# Lab_1_Schematic.net
KiCad netlist of a schematic drawn in EasyEDA Pro
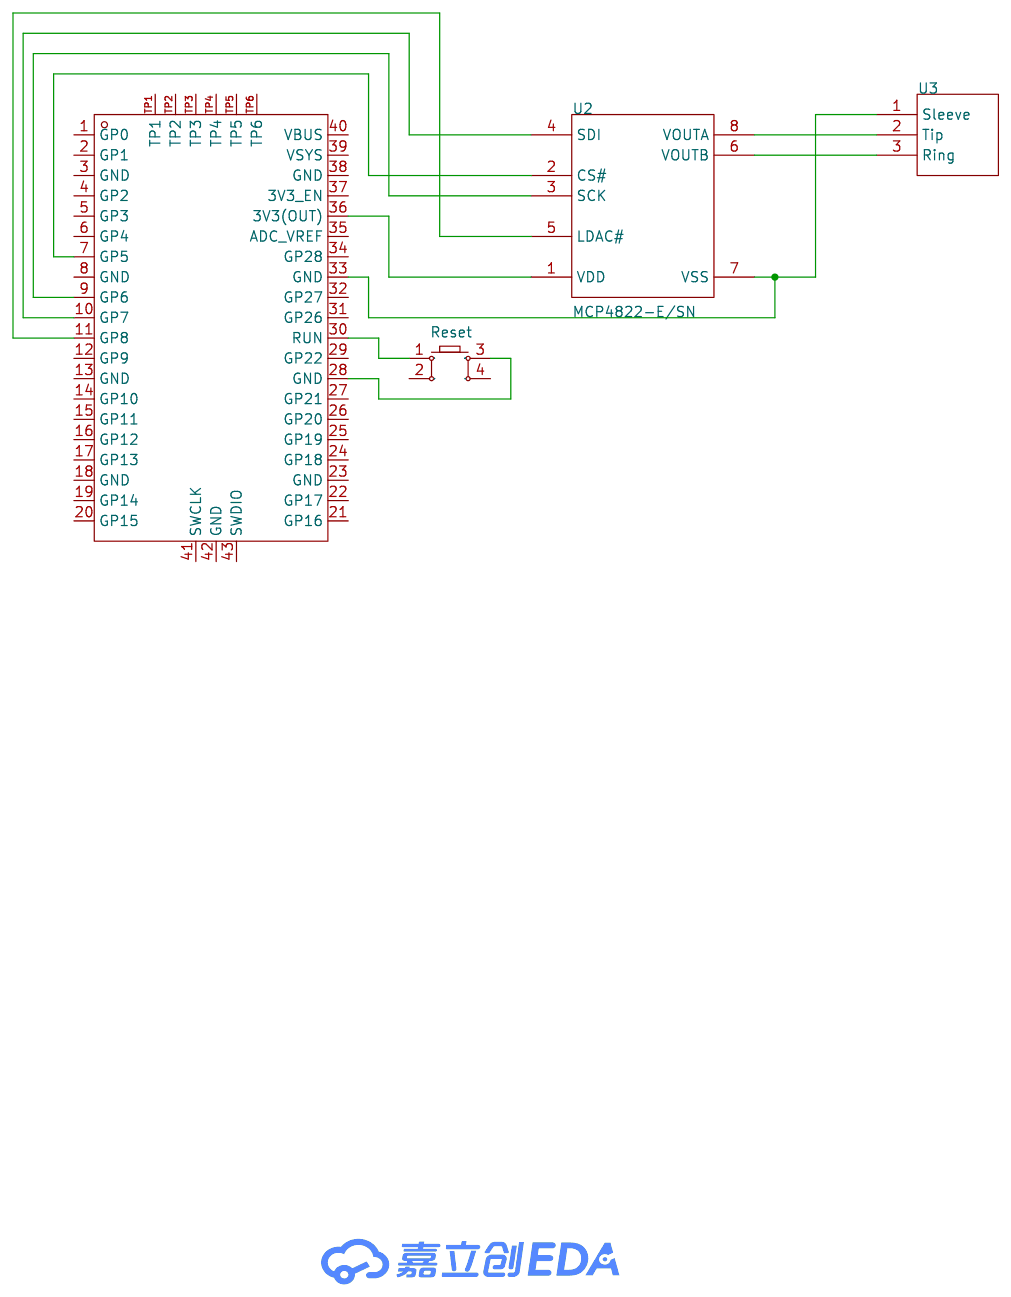
[diagram p0: schematic sheet]

(export (version "E")
  (design (tool "Eeschema 10.0.6"))
  (components
    (comp (ref "Reset")
      (value "~")
      (footprint "easyedapro:Key_SMD_12x12x7.3")
      (libsource (lib "easyedapro") (part "轻触按键"))
    )
    (comp (ref "U1")
      (value "PICO")
      (footprint "easyedapro:COMM-SMD_L51.0-W21.0-P2.54_SC0916")
      (fields (field (name "Manufacturer") "Raspberry Pi(树莓派)"))
      (libsource (lib "easyedapro") (part "PICO"))
    )
    (comp (ref "U2")
      (value "MCP4822-E/SN")
      (footprint "easyedapro:SOIC-8_L4.9-W3.9-P1.27-LS6.0-BL")
      (description "分辨率:12位;接口类型:SPI;工作电压:2.7V~5.5V;稳定时间:4.5us;INL/DNL:12LSB;")
      (fields (field (name "Manufacturer") "MICROCHIP(美国微芯)"))
      (libsource (lib "easyedapro") (part "MCP4822-E/SN"))
    )
    (comp (ref "U3") (value "~") (libsource (lib "easyedapro") (part "3.5mm Socket")))
  )
  (nets
    (net (code "1") (name "Net-(Reset-Pad3)") (class "Default")
      (node (ref "Reset") (pin "3") (pinfunction "3_3") (pintype "input"))
      (node (ref "U1") (pin "28") (pinfunction "GND_28") (pintype "unspecified"))
    )
    (net (code "2") (name "Net-(U1-3V3(OUT))") (class "Default")
      (node (ref "U1") (pin "36") (pinfunction "3V3(OUT)_36") (pintype "unspecified"))
      (node (ref "U2") (pin "1") (pinfunction "VDD_1") (pintype "unspecified"))
    )
    (net (code "3") (name "Net-(U1-GP5)") (class "Default")
      (node (ref "U1") (pin "7") (pinfunction "GP5_7") (pintype "unspecified"))
      (node (ref "U2") (pin "2") (pinfunction "CS#_2") (pintype "unspecified"))
    )
    (net (code "4") (name "Net-(U1-GP6)") (class "Default")
      (node (ref "U1") (pin "9") (pinfunction "GP6_9") (pintype "unspecified"))
      (node (ref "U2") (pin "3") (pinfunction "SCK_3") (pintype "unspecified"))
    )
    (net (code "5") (name "Net-(U1-GP7)") (class "Default")
      (node (ref "U1") (pin "10") (pinfunction "GP7_10") (pintype "unspecified"))
      (node (ref "U2") (pin "4") (pinfunction "SDI_4") (pintype "unspecified"))
    )
    (net (code "6") (name "Net-(U1-GP8)") (class "Default")
      (node (ref "U1") (pin "11") (pinfunction "GP8_11") (pintype "unspecified"))
      (node (ref "U2") (pin "5") (pinfunction "LDAC#_5") (pintype "unspecified"))
    )
    (net (code "7") (name "Net-(U1-RUN)") (class "Default")
      (node (ref "Reset") (pin "1") (pinfunction "1_1") (pintype "input"))
      (node (ref "U1") (pin "30") (pinfunction "RUN_30") (pintype "unspecified"))
    )
    (net (code "8") (name "Net-(U2-VOUTA)") (class "Default")
      (node (ref "U2") (pin "8") (pinfunction "VOUTA_8") (pintype "output"))
      (node (ref "U3") (pin "2") (pinfunction "Tip_2") (pintype "input"))
    )
    (net (code "9") (name "Net-(U2-VOUTB)") (class "Default")
      (node (ref "U2") (pin "6") (pinfunction "VOUTB_6") (pintype "output"))
      (node (ref "U3") (pin "3") (pinfunction "Ring_3") (pintype "input"))
    )
    (net (code "10") (name "Net-(U2-VSS)") (class "Default")
      (node (ref "U1") (pin "33") (pinfunction "GND_33") (pintype "unspecified"))
      (node (ref "U2") (pin "7") (pinfunction "VSS_7") (pintype "unspecified"))
      (node (ref "U3") (pin "1") (pinfunction "Sleeve_1") (pintype "input"))
    )
    (net (code "11") (name "unconnected-(Reset-Pad2)") (class "Default")
      (node (ref "Reset") (pin "2") (pinfunction "2_2") (pintype "input"))
    )
    (net (code "12") (name "unconnected-(Reset-Pad4)") (class "Default")
      (node (ref "Reset") (pin "4") (pinfunction "4_4") (pintype "input"))
    )
    (net (code "13") (name "unconnected-(U1-3V3_EN-Pad37)") (class "Default")
      (node (ref "U1") (pin "37") (pinfunction "3V3_EN_37") (pintype "unspecified"))
    )
    (net (code "14") (name "unconnected-(U1-ADC_VREF-Pad35)") (class "Default")
      (node (ref "U1") (pin "35") (pinfunction "ADC_VREF_35") (pintype "unspecified"))
    )
    (net (code "15") (name "unconnected-(U1-GND-Pad3)") (class "Default")
      (node (ref "U1") (pin "3") (pinfunction "GND_3") (pintype "unspecified"))
    )
    (net (code "16") (name "unconnected-(U1-GND-Pad8)") (class "Default")
      (node (ref "U1") (pin "8") (pinfunction "GND_8") (pintype "unspecified"))
    )
    (net (code "17") (name "unconnected-(U1-GND-Pad13)") (class "Default")
      (node (ref "U1") (pin "13") (pinfunction "GND_13") (pintype "unspecified"))
    )
    (net (code "18") (name "unconnected-(U1-GND-Pad18)") (class "Default")
      (node (ref "U1") (pin "18") (pinfunction "GND_18") (pintype "unspecified"))
    )
    (net (code "19") (name "unconnected-(U1-GND-Pad23)") (class "Default")
      (node (ref "U1") (pin "23") (pinfunction "GND_23") (pintype "unspecified"))
    )
    (net (code "20") (name "unconnected-(U1-GND-Pad38)") (class "Default")
      (node (ref "U1") (pin "38") (pinfunction "GND_38") (pintype "unspecified"))
    )
    (net (code "21") (name "unconnected-(U1-GND-Pad42)") (class "Default")
      (node (ref "U1") (pin "42") (pinfunction "GND_42") (pintype "unspecified"))
    )
    (net (code "22") (name "unconnected-(U1-GP0-Pad1)") (class "Default")
      (node (ref "U1") (pin "1") (pinfunction "GP0_1") (pintype "unspecified"))
    )
    (net (code "23") (name "unconnected-(U1-GP1-Pad2)") (class "Default")
      (node (ref "U1") (pin "2") (pinfunction "GP1_2") (pintype "unspecified"))
    )
    (net (code "24") (name "unconnected-(U1-GP2-Pad4)") (class "Default")
      (node (ref "U1") (pin "4") (pinfunction "GP2_4") (pintype "unspecified"))
    )
    (net (code "25") (name "unconnected-(U1-GP3-Pad5)") (class "Default")
      (node (ref "U1") (pin "5") (pinfunction "GP3_5") (pintype "unspecified"))
    )
    (net (code "26") (name "unconnected-(U1-GP4-Pad6)") (class "Default")
      (node (ref "U1") (pin "6") (pinfunction "GP4_6") (pintype "unspecified"))
    )
    (net (code "27") (name "unconnected-(U1-GP9-Pad12)") (class "Default")
      (node (ref "U1") (pin "12") (pinfunction "GP9_12") (pintype "unspecified"))
    )
    (net (code "28") (name "unconnected-(U1-GP10-Pad14)") (class "Default")
      (node (ref "U1") (pin "14") (pinfunction "GP10_14") (pintype "unspecified"))
    )
    (net (code "29") (name "unconnected-(U1-GP11-Pad15)") (class "Default")
      (node (ref "U1") (pin "15") (pinfunction "GP11_15") (pintype "unspecified"))
    )
    (net (code "30") (name "unconnected-(U1-GP12-Pad16)") (class "Default")
      (node (ref "U1") (pin "16") (pinfunction "GP12_16") (pintype "unspecified"))
    )
    (net (code "31") (name "unconnected-(U1-GP13-Pad17)") (class "Default")
      (node (ref "U1") (pin "17") (pinfunction "GP13_17") (pintype "unspecified"))
    )
    (net (code "32") (name "unconnected-(U1-GP14-Pad19)") (class "Default")
      (node (ref "U1") (pin "19") (pinfunction "GP14_19") (pintype "unspecified"))
    )
    (net (code "33") (name "unconnected-(U1-GP15-Pad20)") (class "Default")
      (node (ref "U1") (pin "20") (pinfunction "GP15_20") (pintype "unspecified"))
    )
    (net (code "34") (name "unconnected-(U1-GP16-Pad21)") (class "Default")
      (node (ref "U1") (pin "21") (pinfunction "GP16_21") (pintype "unspecified"))
    )
    (net (code "35") (name "unconnected-(U1-GP17-Pad22)") (class "Default")
      (node (ref "U1") (pin "22") (pinfunction "GP17_22") (pintype "unspecified"))
    )
    (net (code "36") (name "unconnected-(U1-GP18-Pad24)") (class "Default")
      (node (ref "U1") (pin "24") (pinfunction "GP18_24") (pintype "unspecified"))
    )
    (net (code "37") (name "unconnected-(U1-GP19-Pad25)") (class "Default")
      (node (ref "U1") (pin "25") (pinfunction "GP19_25") (pintype "unspecified"))
    )
    (net (code "38") (name "unconnected-(U1-GP20-Pad26)") (class "Default")
      (node (ref "U1") (pin "26") (pinfunction "GP20_26") (pintype "unspecified"))
    )
    (net (code "39") (name "unconnected-(U1-GP21-Pad27)") (class "Default")
      (node (ref "U1") (pin "27") (pinfunction "GP21_27") (pintype "unspecified"))
    )
    (net (code "40") (name "unconnected-(U1-GP22-Pad29)") (class "Default")
      (node (ref "U1") (pin "29") (pinfunction "GP22_29") (pintype "unspecified"))
    )
    (net (code "41") (name "unconnected-(U1-GP26-Pad31)") (class "Default")
      (node (ref "U1") (pin "31") (pinfunction "GP26_31") (pintype "unspecified"))
    )
    (net (code "42") (name "unconnected-(U1-GP27-Pad32)") (class "Default")
      (node (ref "U1") (pin "32") (pinfunction "GP27_32") (pintype "unspecified"))
    )
    (net (code "43") (name "unconnected-(U1-GP28-Pad34)") (class "Default")
      (node (ref "U1") (pin "34") (pinfunction "GP28_34") (pintype "unspecified"))
    )
    (net (code "44") (name "unconnected-(U1-PadTP1)") (class "Default")
      (node (ref "U1") (pin "TP1") (pinfunction "TP1_TP1") (pintype "unspecified"))
    )
    (net (code "45") (name "unconnected-(U1-PadTP2)") (class "Default")
      (node (ref "U1") (pin "TP2") (pinfunction "TP2_TP2") (pintype "unspecified"))
    )
    (net (code "46") (name "unconnected-(U1-PadTP3)") (class "Default")
      (node (ref "U1") (pin "TP3") (pinfunction "TP3_TP3") (pintype "unspecified"))
    )
    (net (code "47") (name "unconnected-(U1-PadTP4)") (class "Default")
      (node (ref "U1") (pin "TP4") (pinfunction "TP4_TP4") (pintype "unspecified"))
    )
    (net (code "48") (name "unconnected-(U1-PadTP5)") (class "Default")
      (node (ref "U1") (pin "TP5") (pinfunction "TP5_TP5") (pintype "unspecified"))
    )
    (net (code "49") (name "unconnected-(U1-PadTP6)") (class "Default")
      (node (ref "U1") (pin "TP6") (pinfunction "TP6_TP6") (pintype "unspecified"))
    )
    (net (code "50") (name "unconnected-(U1-SWCLK-Pad41)") (class "Default")
      (node (ref "U1") (pin "41") (pinfunction "SWCLK_41") (pintype "unspecified"))
    )
    (net (code "51") (name "unconnected-(U1-SWDIO-Pad43)") (class "Default")
      (node (ref "U1") (pin "43") (pinfunction "SWDIO_43") (pintype "unspecified"))
    )
    (net (code "52") (name "unconnected-(U1-VBUS-Pad40)") (class "Default")
      (node (ref "U1") (pin "40") (pinfunction "VBUS_40") (pintype "unspecified"))
    )
    (net (code "53") (name "unconnected-(U1-VSYS-Pad39)") (class "Default")
      (node (ref "U1") (pin "39") (pinfunction "VSYS_39") (pintype "unspecified"))
    )
  )
)
